# 04_MCU_ANALOG.net
KiCad netlist of a schematic drawn in Altium Designer
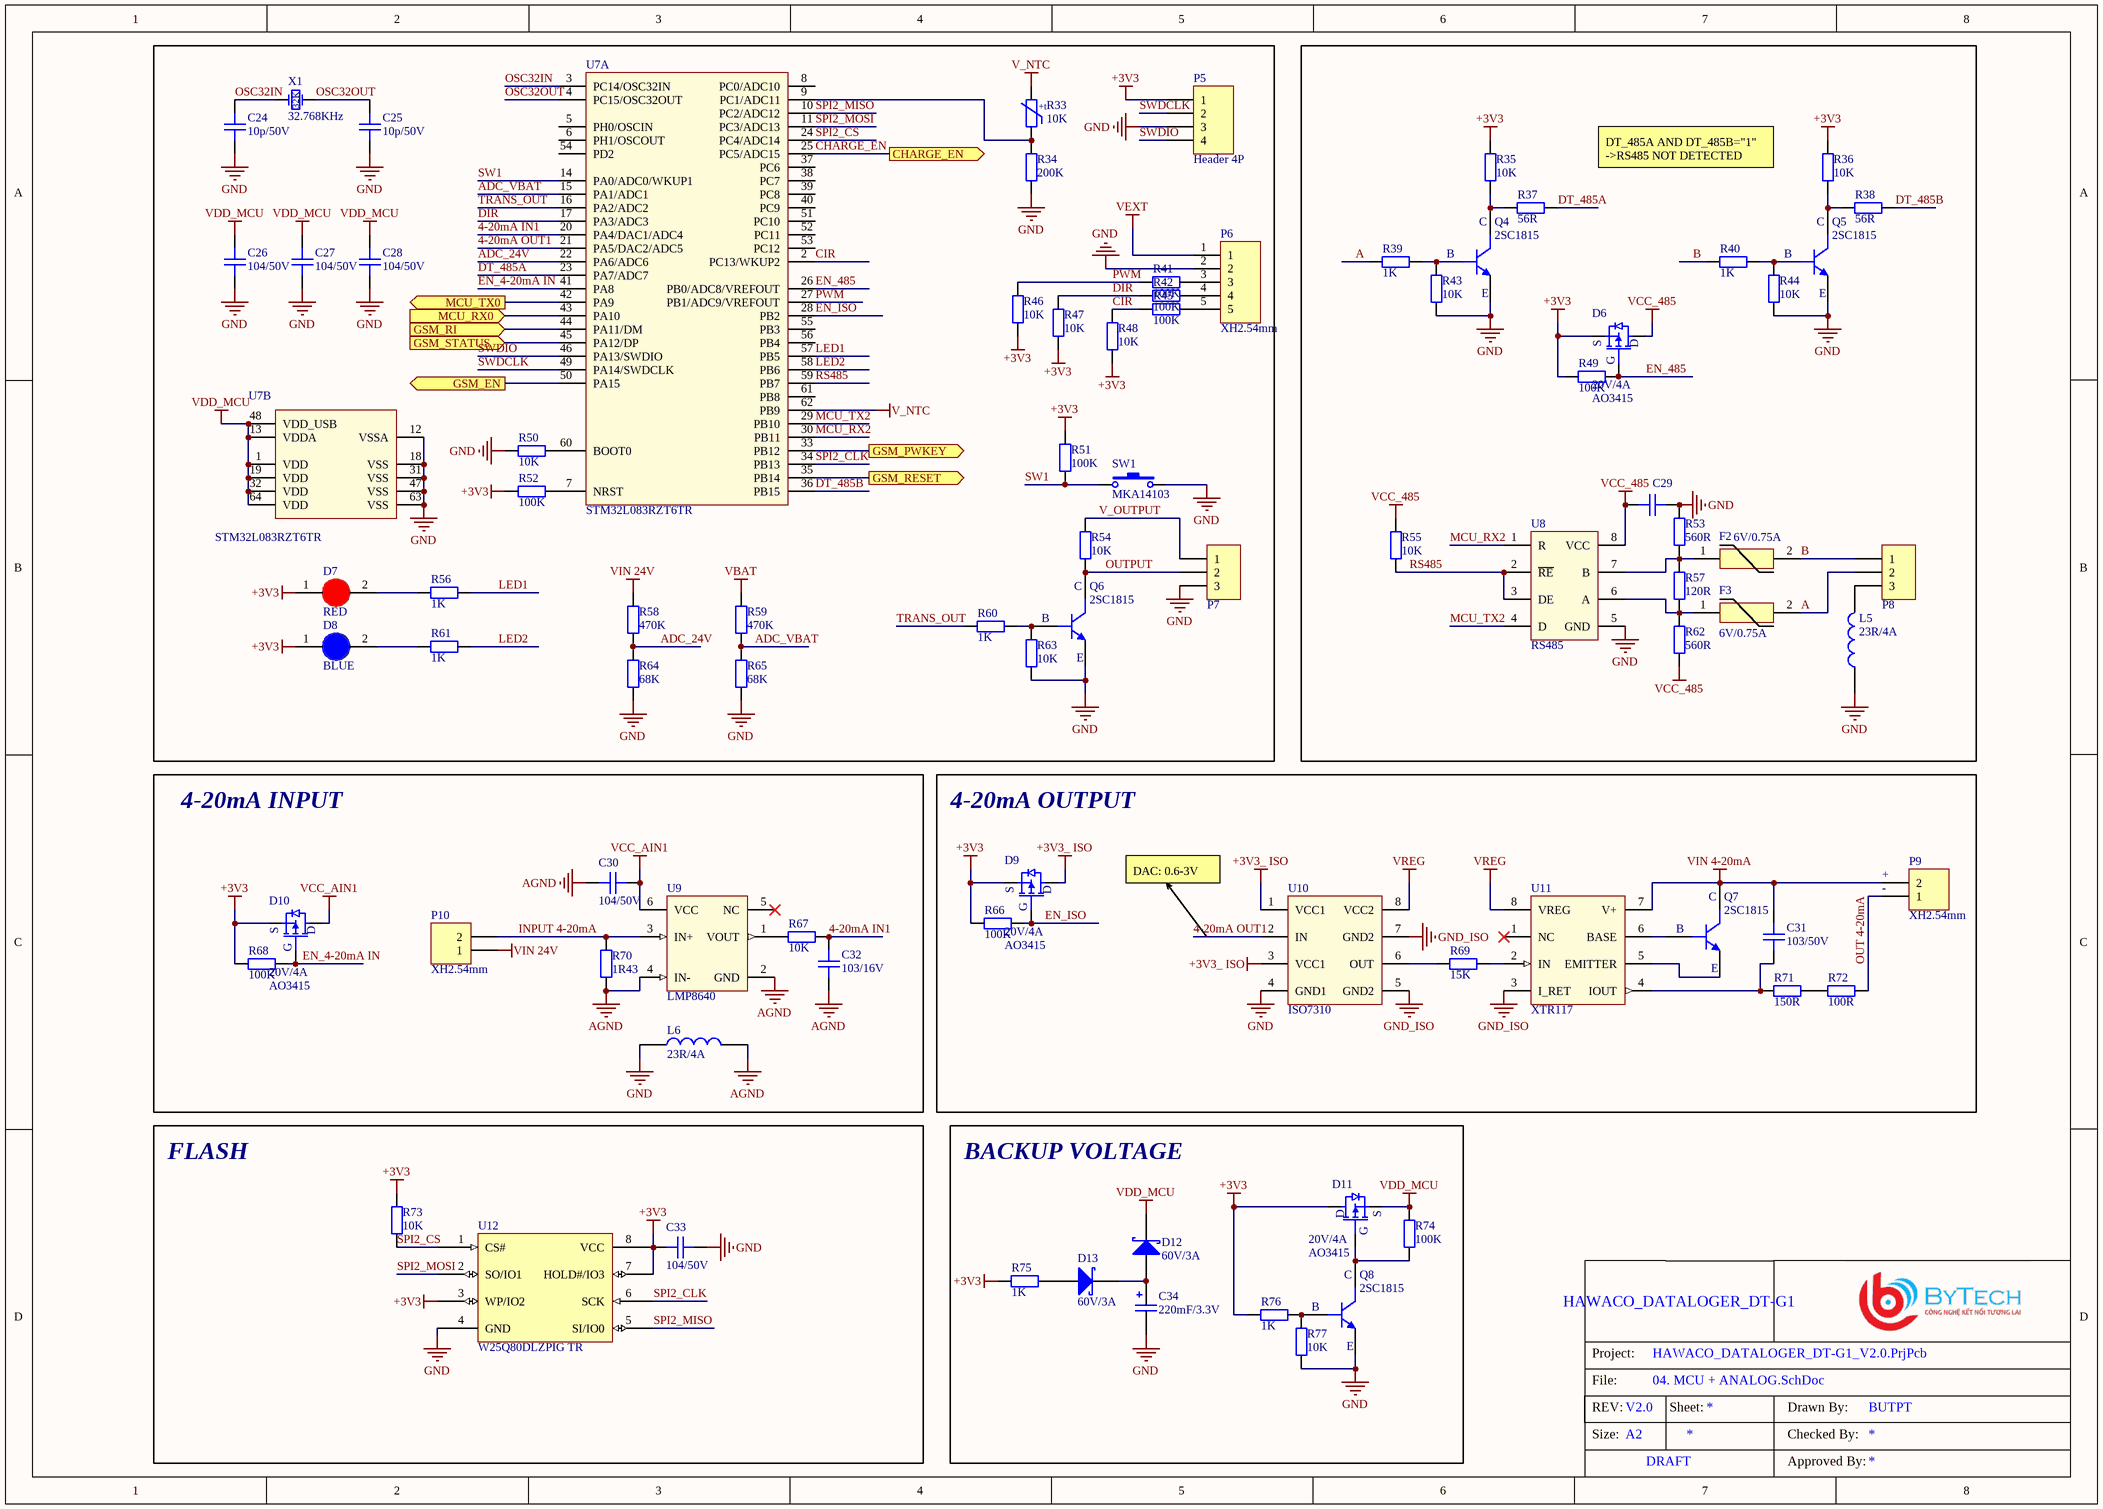
[diagram p0: 04. MCU + ANALOG.SchDoc]

(export (version "E")
  (design (tool "Eeschema 10.0.6"))
  (components
    (comp (ref "C24")
      (value "10p/50V")
      (footprint "CAPC-0603 (1608)")
      (description "CAP CER 10pF 5% 50V NP0 0603")
      (fields (field (name "MPN") "CL10C100JB8NNND"))
      (libsource (lib "01.Passives") (part "CL10C100JB8NNND"))
    )
    (comp (ref "C25")
      (value "10p/50V")
      (footprint "CAPC-0603 (1608)")
      (description "CAP CER 10pF 5% 50V NP0 0603")
      (fields (field (name "MPN") "CL10C100JB8NNND"))
      (libsource (lib "01.Passives") (part "CL10C100JB8NNND"))
    )
    (comp (ref "C26")
      (value "104/50V")
      (footprint "CAPC-0603 (1608)")
      (description "CAP CER 0.1uF 50V 10% X7R 0603")
      (fields (field (name "MPN") "C0603C104K5RACTU"))
      (libsource (lib "01.Passives") (part "C0603C104K5RACTU"))
    )
    (comp (ref "C27")
      (value "104/50V")
      (footprint "CAPC-0603 (1608)")
      (description "CAP CER 0.1uF 50V 10% X7R 0603")
      (fields (field (name "MPN") "C0603C104K5RACTU"))
      (libsource (lib "01.Passives") (part "C0603C104K5RACTU"))
    )
    (comp (ref "C28")
      (value "104/50V")
      (footprint "CAPC-0603 (1608)")
      (description "CAP CER 0.1uF 50V 10% X7R 0603")
      (fields (field (name "MPN") "C0603C104K5RACTU"))
      (libsource (lib "01.Passives") (part "C0603C104K5RACTU"))
    )
    (comp (ref "C29")
      (value "104/50V")
      (footprint "CAPC-0603 (1608)")
      (description "CAP CER 0.1uF 50V 10% X7R 0603")
      (fields (field (name "MPN") "C0603C104K5RACTU"))
      (libsource (lib "01.Passives") (part "C0603C104K5RACTU"))
    )
    (comp (ref "C30")
      (value "104/50V")
      (footprint "CAPC-0603 (1608)")
      (description "CAP CER 0.1uF 50V 10% X7R 0603")
      (fields (field (name "MPN") "C0603C104K5RACTU"))
      (libsource (lib "01.Passives") (part "C0603C104K5RACTU"))
    )
    (comp (ref "C31")
      (value "103/50V")
      (footprint "CAPC-0805 (2012)")
      (description "CAP CER 10nF 10% 50V X7R 0805")
      (fields (field (name "MPN") "CL21B103KBANNNC"))
      (libsource (lib "01.Passives") (part "CL21B103KBANNNC"))
    )
    (comp (ref "C32")
      (value "103/16V")
      (footprint "CAPC-0603 (1608)")
      (description "CAP CER 10nF 16V 10% X7R 0603")
      (fields (field (name "MPN") "CC0603KRX7R7BB103"))
      (libsource (lib "01.Passives") (part "CC0603KRX7R7BB103"))
    )
    (comp (ref "C33")
      (value "104/50V")
      (footprint "CAPC-0603 (1608)")
      (description "CAP CER 0.1uF 50V 10% X7R 0603")
      (fields (field (name "MPN") "C0603C104K5RACTU"))
      (libsource (lib "01.Passives") (part "C0603C104K5RACTU"))
    )
    (comp (ref "C34")
      (value "220mF/3.3V")
      (footprint "CAP-SUPER-0.22F")
      (description "CAP 220mF SUPER -20% +80% 3.3V SMD")
      (fields (field (name "MPN") "DCK-3R3E224U-E"))
      (libsource (lib "01.Passives") (part "DCK-3R3E224U-E"))
    )
    (comp (ref "D6")
      (value "20V/4A")
      (footprint "SOT23_3")
      (description "MOSFET P-CH 20V 4A SOT23")
      (fields (field (name "MFR") "Alpha & Omega Semiconductor Inc.") (field (name "MPN") "AO3415"))
      (libsource (lib "03.Semiconductor") (part "AO3415"))
    )
    (comp (ref "D7")
      (value "RED")
      (footprint "LED 0603")
      (description "LED 0603 RED")
      (libsource (lib "03.Semiconductor") (part "LED 0603 RED"))
    )
    (comp (ref "D8")
      (value "BLUE")
      (footprint "LED 0603")
      (description "LED 0603 BLUE")
      (libsource (lib "03.Semiconductor") (part "LED 0603 BLUE"))
    )
    (comp (ref "D9")
      (value "20V/4A")
      (footprint "SOT23_3")
      (description "MOSFET P-CH 20V 4A SOT23")
      (fields (field (name "MFR") "Alpha & Omega Semiconductor Inc.") (field (name "MPN") "AO3415"))
      (libsource (lib "03.Semiconductor") (part "AO3415"))
    )
    (comp (ref "D10")
      (value "20V/4A")
      (footprint "SOT23_3")
      (description "MOSFET P-CH 20V 4A SOT23")
      (fields (field (name "MFR") "Alpha & Omega Semiconductor Inc.") (field (name "MPN") "AO3415"))
      (libsource (lib "03.Semiconductor") (part "AO3415"))
    )
    (comp (ref "D11")
      (value "20V/4A")
      (footprint "SOT23_3")
      (description "MOSFET P-CH 20V 4A SOT23")
      (fields (field (name "MFR") "Alpha & Omega Semiconductor Inc.") (field (name "MPN") "AO3415"))
      (libsource (lib "03.Semiconductor") (part "AO3415"))
    )
    (comp (ref "D12")
      (value "60V/3A")
      (footprint "DIODE_DO214AC_SMA")
      (description "DIODE SCHOTTKY 60V 3A DO214AC")
      (fields (field (name "MPN") "SK36A-LTP"))
      (libsource (lib "03.Semiconductor") (part "SK36A-LTP"))
    )
    (comp (ref "D13")
      (value "60V/3A")
      (footprint "DIODE_DO214AC_SMA")
      (description "DIODE SCHOTTKY 60V 3A DO214AC")
      (fields (field (name "MPN") "SK36A-LTP"))
      (libsource (lib "03.Semiconductor") (part "SK36A-LTP"))
    )
    (comp (ref "F2")
      (value "6V/0.75A")
      (footprint "FUSE 0ZCK_BEL")
      (description "PTC RESET FUSE 6V 750MA 0805")
      (fields (field (name "MPN") "0ZCK0075FF2E") (field (name "MANUFACTURER") "Bel Fuse Inc."))
      (libsource (lib "02.Power,Protection") (part "0ZCK0075FF2E"))
    )
    (comp (ref "F3")
      (value "6V/0.75A")
      (footprint "FUSE 0ZCK_BEL")
      (description "PTC RESET FUSE 6V 750MA 0805")
      (fields (field (name "MPN") "0ZCK0075FF2E") (field (name "MANUFACTURER") "Bel Fuse Inc."))
      (libsource (lib "02.Power,Protection") (part "0ZCK0075FF2E"))
    )
    (comp (ref "L5")
      (value "23R/4A")
      (footprint "IND-0603 (1608)")
      (description "IND-FERRITE BEAD 23 OHM  4A 0603 1LN")
      (fields (field (name "MPN") "FBMJ1608HM230NT"))
      (libsource (lib "01.Passives") (part "FBMJ1608HM230NT"))
    )
    (comp (ref "L6")
      (value "23R/4A")
      (footprint "IND-0603 (1608)")
      (description "IND-FERRITE BEAD 23 OHM  4A 0603 1LN")
      (fields (field (name "MPN") "FBMJ1608HM230NT"))
      (libsource (lib "01.Passives") (part "FBMJ1608HM230NT"))
    )
    (comp (ref "P5")
      (value "Header 4P")
      (footprint "HDR1X4")
      (description "Header, 4 Pin Pitch 2.54mm")
      (fields (field (name "MPN") "S1012EC-40-ND"))
      (libsource (lib "04.Header-Connecter") (part "Header 4x1"))
    )
    (comp (ref "P6")
      (value "XH2.54mm")
      (footprint "XH2.54-5P")
      (description "XH2.54mmm - 5P 180 degree")
      (fields (field (name "MPN") "XH2.54-5P") (field (name "MFR") "CHINA"))
      (libsource (lib "04.Header-Connecter") (part "XH2.54-5P"))
    )
    (comp (ref "P7")
      (value "RS485")
      (footprint "XH2.54-3P")
      (description "Header XH2.54mm 3P")
      (fields (field (name "MPN") "CLA1879") (field (name "MFR") "China Brand"))
      (libsource (lib "04.Header-Connecter") (part "Header XH2.54 - 3P"))
    )
    (comp (ref "P8")
      (value "RS485")
      (footprint "XH2.54-3P")
      (description "Header XH2.54mm 3P")
      (fields (field (name "MPN") "CLA1879") (field (name "MFR") "China Brand"))
      (libsource (lib "04.Header-Connecter") (part "Header XH2.54 - 3P"))
    )
    (comp (ref "P9")
      (value "XH2.54mm")
      (footprint "XH2.54-2P")
      (description "XH2.54mmm - 2P 180 degree")
      (fields (field (name "MPN") "XH-2A"))
      (libsource (lib "04.Header-Connecter") (part "XH-2A"))
    )
    (comp (ref "P10")
      (value "XH2.54mm")
      (footprint "XH2.54-2P")
      (description "XH2.54mmm - 2P 180 degree")
      (fields (field (name "MPN") "XH-2A"))
      (libsource (lib "") (part "XH-2A_1"))
    )
    (comp (ref "Q4")
      (value "2SC1815")
      (footprint "SOT23_3")
      (description "TRANS NPN 50V 0.15A SOT23-3")
      (libsource (lib "03.Semiconductor") (part "2SC1815"))
    )
    (comp (ref "Q5")
      (value "2SC1815")
      (footprint "SOT23_3")
      (description "TRANS NPN 50V 0.15A SOT23-3")
      (libsource (lib "03.Semiconductor") (part "2SC1815"))
    )
    (comp (ref "Q6")
      (value "2SC1815")
      (footprint "SOT23_3")
      (description "TRANS NPN 50V 0.15A SOT23-3")
      (libsource (lib "03.Semiconductor") (part "2SC1815"))
    )
    (comp (ref "Q7")
      (value "2SC1815")
      (footprint "SOT23_3")
      (description "TRANS NPN 50V 0.15A SOT23-3")
      (libsource (lib "03.Semiconductor") (part "2SC1815"))
    )
    (comp (ref "Q8")
      (value "2SC1815")
      (footprint "SOT23_3")
      (description "TRANS NPN 50V 0.15A SOT23-3")
      (libsource (lib "03.Semiconductor") (part "2SC1815"))
    )
    (comp (ref "R33")
      (value "10K")
      (footprint "RES NTC 10K")
      (description "THERMISTOR NTC 10KOHM 3964K BEAD")
      (fields (field (name "MPN") "01M1002JF") (field (name "MFR") "Vishay"))
      (libsource (lib "01.Passives") (part "01M1002JF"))
    )
    (comp (ref "R34")
      (value "200K")
      (footprint "RESC-0603 (1608)")
      (description "RES SMD 200K OHM 1% 1/10W 0603")
      (fields (field (name "MPN") "CR0603-FX-2003ELF"))
      (libsource (lib "01.Passives") (part "CR0603-FX-2003ELF"))
    )
    (comp (ref "R35")
      (value "10K")
      (footprint "RESC-0603 (1608)")
      (description "RES SMD 10K OHM 1% 1/10W 0603")
      (fields (field (name "MPN") "RC0603FR-0710KL"))
      (libsource (lib "01.Passives") (part "RC0603FR-0710KL"))
    )
    (comp (ref "R36")
      (value "10K")
      (footprint "RESC-0603 (1608)")
      (description "RES SMD 10K OHM 1% 1/10W 0603")
      (fields (field (name "MPN") "RC0603FR-0710KL"))
      (libsource (lib "01.Passives") (part "RC0603FR-0710KL"))
    )
    (comp (ref "R37")
      (value "56R")
      (footprint "RESC-0603 (1608)")
      (description "RES SMD 56 OHM 5% 1/10W 0603")
      (fields (field (name "MPN") "RC0603JR-0756RL"))
      (libsource (lib "01.Passives") (part "RC0603JR-0756RL"))
    )
    (comp (ref "R38")
      (value "56R")
      (footprint "RESC-0603 (1608)")
      (description "RES SMD 56 OHM 5% 1/10W 0603")
      (fields (field (name "MPN") "RC0603JR-0756RL"))
      (libsource (lib "01.Passives") (part "RC0603JR-0756RL"))
    )
    (comp (ref "R39")
      (value "1K")
      (footprint "RESC-0603 (1608)")
      (description "RES SMD 1 KOHM 1% 1/10W 0603")
      (fields (field (name "MPN") "RC0603FR-071KL"))
      (libsource (lib "01.Passives") (part "RC0603FR-071KL"))
    )
    (comp (ref "R40")
      (value "1K")
      (footprint "RESC-0603 (1608)")
      (description "RES SMD 1 KOHM 1% 1/10W 0603")
      (fields (field (name "MPN") "RC0603FR-071KL"))
      (libsource (lib "01.Passives") (part "RC0603FR-071KL"))
    )
    (comp (ref "R41")
      (value "100K")
      (footprint "RESC-0603 (1608)")
      (description "RES SMD 100K OHM 1% 1/10W 0603")
      (fields (field (name "MPN") "RC0603FR-07100KL"))
      (libsource (lib "") (part "RC0603FR-07100KL_3"))
    )
    (comp (ref "R42")
      (value "100K")
      (footprint "RESC-0603 (1608)")
      (description "RES SMD 100K OHM 1% 1/10W 0603")
      (fields (field (name "MPN") "RC0603FR-07100KL"))
      (libsource (lib "") (part "RC0603FR-07100KL_3"))
    )
    (comp (ref "R43")
      (value "10K")
      (footprint "RESC-0603 (1608)")
      (description "RES SMD 10K OHM 1% 1/10W 0603")
      (fields (field (name "MPN") "RC0603FR-0710KL"))
      (libsource (lib "01.Passives") (part "RC0603FR-0710KL"))
    )
    (comp (ref "R44")
      (value "10K")
      (footprint "RESC-0603 (1608)")
      (description "RES SMD 10K OHM 1% 1/10W 0603")
      (fields (field (name "MPN") "RC0603FR-0710KL"))
      (libsource (lib "01.Passives") (part "RC0603FR-0710KL"))
    )
    (comp (ref "R45")
      (value "100K")
      (footprint "RESC-0603 (1608)")
      (description "RES SMD 100K OHM 1% 1/10W 0603")
      (fields (field (name "MPN") "RC0603FR-07100KL"))
      (libsource (lib "") (part "RC0603FR-07100KL_3"))
    )
    (comp (ref "R46")
      (value "10K")
      (footprint "RESC-0603 (1608)")
      (description "RES SMD 10K OHM 1% 1/10W 0603")
      (fields (field (name "MPN") "RC0603FR-0710KL"))
      (libsource (lib "01.Passives") (part "RC0603FR-0710KL"))
    )
    (comp (ref "R47")
      (value "10K")
      (footprint "RESC-0603 (1608)")
      (description "RES SMD 10K OHM 1% 1/10W 0603")
      (fields (field (name "MPN") "RC0603FR-0710KL"))
      (libsource (lib "01.Passives") (part "RC0603FR-0710KL"))
    )
    (comp (ref "R48")
      (value "10K")
      (footprint "RESC-0603 (1608)")
      (description "RES SMD 10K OHM 1% 1/10W 0603")
      (fields (field (name "MPN") "RC0603FR-0710KL"))
      (libsource (lib "01.Passives") (part "RC0603FR-0710KL"))
    )
    (comp (ref "R49")
      (value "100K")
      (footprint "RESC-0603 (1608)")
      (description "RES SMD 100K OHM 1% 1/10W 0603")
      (fields (field (name "MPN") "RC0603FR-07100KL"))
      (libsource (lib "") (part "RC0603FR-07100KL_1"))
    )
    (comp (ref "R50")
      (value "10K")
      (footprint "RESC-0603 (1608)")
      (description "RES SMD 10K OHM 1% 1/10W 0603")
      (fields (field (name "MPN") "RC0603FR-0710KL"))
      (libsource (lib "") (part "RC0603FR-0710KL_1"))
    )
    (comp (ref "R51")
      (value "100K")
      (footprint "RESC-0603 (1608)")
      (description "RES SMD 100K OHM 1% 1/10W 0603")
      (fields (field (name "MPN") "RC0603FR-07100KL"))
      (libsource (lib "01.Passives") (part "RC0603FR-07100KL"))
    )
    (comp (ref "R52")
      (value "100K")
      (footprint "RESC-0603 (1608)")
      (description "RES SMD 100K OHM 1% 1/10W 0603")
      (fields (field (name "MPN") "RC0603FR-07100KL"))
      (libsource (lib "01.Passives") (part "RC0603FR-07100KL"))
    )
    (comp (ref "R53")
      (value "560R")
      (footprint "RESC-0603 (1608)")
      (description "RES SMD 560 OHM 1% 1/10W 0603")
      (fields (field (name "MPN") "RC0603FR-07560RL"))
      (libsource (lib "01.Passives") (part "RC0603FR-07560RL"))
    )
    (comp (ref "R54")
      (value "10K")
      (footprint "RESC-0603 (1608)")
      (description "RES SMD 10K OHM 1% 1/10W 0603")
      (fields (field (name "MPN") "RC0603FR-0710KL"))
      (libsource (lib "01.Passives") (part "RC0603FR-0710KL"))
    )
    (comp (ref "R55")
      (value "10K")
      (footprint "RESC-0603 (1608)")
      (description "RES SMD 10K OHM 1% 1/10W 0603")
      (fields (field (name "MPN") "RC0603FR-0710KL"))
      (libsource (lib "01.Passives") (part "RC0603FR-0710KL"))
    )
    (comp (ref "R56")
      (value "1K")
      (footprint "RESC-0603 (1608)")
      (description "RES SMD 1 KOHM 1% 1/10W 0603")
      (fields (field (name "MPN") "RC0603FR-071KL"))
      (libsource (lib "01.Passives") (part "RC0603FR-071KL"))
    )
    (comp (ref "R57")
      (value "120R")
      (footprint "RESC-0603 (1608)")
      (description "RES SMD 120 OHM 1% 1/10W 0603")
      (fields (field (name "MPN") "RC0603FR-07120RL"))
      (libsource (lib "01.Passives") (part "RC0603FR-07120RL"))
    )
    (comp (ref "R58")
      (value "470K")
      (footprint "RESC-0603 (1608)")
      (description "RES SMD 470K OHM 1% 1/10W 0603")
      (fields (field (name "MPN") "RC0603FR-07470K"))
      (libsource (lib "01.Passives") (part "RC0603FR-07470KL"))
    )
    (comp (ref "R59")
      (value "470K")
      (footprint "RESC-0603 (1608)")
      (description "RES SMD 470K OHM 1% 1/10W 0603")
      (fields (field (name "MPN") "RC0603FR-07470K"))
      (libsource (lib "01.Passives") (part "RC0603FR-07470KL"))
    )
    (comp (ref "R60")
      (value "1K")
      (footprint "RESC-0603 (1608)")
      (description "RES SMD 1 KOHM 1% 1/10W 0603")
      (fields (field (name "MPN") "RC0603FR-071KL"))
      (libsource (lib "01.Passives") (part "RC0603FR-071KL"))
    )
    (comp (ref "R61")
      (value "1K")
      (footprint "RESC-0603 (1608)")
      (description "RES SMD 1 KOHM 1% 1/10W 0603")
      (fields (field (name "MPN") "RC0603FR-071KL"))
      (libsource (lib "01.Passives") (part "RC0603FR-071KL"))
    )
    (comp (ref "R62")
      (value "560R")
      (footprint "RESC-0603 (1608)")
      (description "RES SMD 560 OHM 1% 1/10W 0603")
      (fields (field (name "MPN") "RC0603FR-07560RL"))
      (libsource (lib "01.Passives") (part "RC0603FR-07560RL"))
    )
    (comp (ref "R63")
      (value "10K")
      (footprint "RESC-0603 (1608)")
      (description "RES SMD 10K OHM 1% 1/10W 0603")
      (fields (field (name "MPN") "RC0603FR-0710KL"))
      (libsource (lib "01.Passives") (part "RC0603FR-0710KL"))
    )
    (comp (ref "R64")
      (value "68K")
      (footprint "RESC-0603 (1608)")
      (description "RES SMD 68K OHM 1% 1/10W 0603")
      (fields (field (name "MPN") "CRCW060368K0FKEA"))
      (libsource (lib "01.Passives") (part "CRCW060368K0FKEA"))
    )
    (comp (ref "R65")
      (value "68K")
      (footprint "RESC-0603 (1608)")
      (description "RES SMD 68K OHM 1% 1/10W 0603")
      (fields (field (name "MPN") "CRCW060368K0FKEA"))
      (libsource (lib "01.Passives") (part "CRCW060368K0FKEA"))
    )
    (comp (ref "R66")
      (value "100K")
      (footprint "RESC-0603 (1608)")
      (description "RES SMD 100K OHM 1% 1/10W 0603")
      (fields (field (name "MPN") "RC0603FR-07100KL"))
      (libsource (lib "") (part "RC0603FR-07100KL_1"))
    )
    (comp (ref "R67")
      (value "10K")
      (footprint "RESC-0603 (1608)")
      (description "RES SMD 10K OHM 1% 1/10W 0603")
      (fields (field (name "MPN") "RC0603FR-0710KL"))
      (libsource (lib "") (part "RC0603FR-0710KL_2"))
    )
    (comp (ref "R68")
      (value "100K")
      (footprint "RESC-0603 (1608)")
      (description "RES SMD 100K OHM 1% 1/10W 0603")
      (fields (field (name "MPN") "RC0603FR-07100KL"))
      (libsource (lib "") (part "RC0603FR-07100KL_1"))
    )
    (comp (ref "R69")
      (value "15K")
      (footprint "RESC-0603 (1608)")
      (description "RES SMD 15K OHM 0.1% 1/10W 0603")
      (fields (field (name "MPN") "RT0603BRE-0715KL"))
      (libsource (lib "01.Passives") (part "RT0603BRE-0715KL"))
    )
    (comp (ref "R70")
      (value "1R43")
      (footprint "RESC-0603 (1608)")
      (description "RES SMD 1.43 OHM 0.1% 1/10W 0603")
      (fields (field (name "MPN") "RT0603BRE071R43L") (field (name "MFR") "YAGEO"))
      (libsource (lib "01.Passives") (part "RT0603BRE071R43L"))
    )
    (comp (ref "R71")
      (value "150R")
      (footprint "RESC-0603 (1608)")
      (description "RES SMD 150 OHM 1% 1/10W 0603")
      (fields (field (name "MPN") "RC0603FR-07150RP") (field (name "MFR") "YAGEO"))
      (libsource (lib "01.Passives") (part "RC0603FR-07150RP"))
    )
    (comp (ref "R72")
      (value "100R")
      (footprint "RESC-0603 (1608)")
      (description "RES SMD 100 OHM 1% 1/10W 0603")
      (fields (field (name "MPN") "RC0603FR-07100RL"))
      (libsource (lib "01.Passives") (part "RC0603FR-07100RL"))
    )
    (comp (ref "R73")
      (value "10K")
      (footprint "RESC-0603 (1608)")
      (description "RES SMD 10K OHM 1% 1/10W 0603")
      (fields (field (name "MPN") "RC0603FR-0710KL"))
      (libsource (lib "") (part "RC0603FR-0710KL_1"))
    )
    (comp (ref "R74")
      (value "100K")
      (footprint "RESC-0603 (1608)")
      (description "RES SMD 100K OHM 1% 1/10W 0603")
      (fields (field (name "MPN") "RC0603FR-07100KL"))
      (libsource (lib "") (part "RC0603FR-07100KL_2"))
    )
    (comp (ref "R75")
      (value "1K")
      (footprint "RESC-0603 (1608)")
      (description "RES SMD 1 KOHM 1% 1/10W 0603")
      (fields (field (name "MPN") "RC0603FR-071KL"))
      (libsource (lib "") (part "RC0603FR-071KL_1"))
    )
    (comp (ref "R76")
      (value "1K")
      (footprint "RESC-0603 (1608)")
      (description "RES SMD 1 KOHM 1% 1/10W 0603")
      (fields (field (name "MPN") "RC0603FR-071KL"))
      (libsource (lib "01.Passives") (part "RC0603FR-071KL"))
    )
    (comp (ref "R77")
      (value "10K")
      (footprint "RESC-0603 (1608)")
      (description "RES SMD 10K OHM 1% 1/10W 0603")
      (fields (field (name "MPN") "RC0603FR-0710KL"))
      (libsource (lib "01.Passives") (part "RC0603FR-0710KL"))
    )
    (comp (ref "SW1")
      (value "MKA14103")
      (footprint "MKA-14103")
      (description "switch magnetic control switch 14103 2*14MM")
      (fields (field (name "MFR") "CHINA"))
      (libsource (lib "08.Miscellaneous") (part "MKA14103"))
    )
    (comp (ref "U7")
      (value "STM32L083RZT6TR")
      (footprint "LQFP-64")
      (description "IC MCU 32BIT 192KB FLASH 64LQFP")
      (fields (field (name "MFR") "ST"))
      (libsource (lib "05.IC") (part "STM32L083RZT6TR"))
    )
    (comp (ref "U8")
      (value "RS485")
      (footprint "SOIC8")
      (description "IC TRANSCEIVER HALF 1/1 8SOIC")
      (fields (field (name "MPN") "SN65HVD72DR") (field (name "MFR") "TI"))
      (libsource (lib "05.IC") (part "SN65HVD72DR"))
    )
    (comp (ref "U9")
      (value "LMP8640")
      (footprint "SOT23-6")
      (description "IC CURR SENSE 1 CIRCUIT TSOT23-6")
      (fields (field (name "MPN") "LMP8640MK-H/NOPB") (field (name "MFR") "TI"))
      (libsource (lib "05.IC") (part "LMP8640MK-H/NOPB"))
    )
    (comp (ref "U10")
      (value "ISO7310")
      (footprint "SOIC-8")
      (description "DGTL ISO 3000VRMS 1CH 8SOIC")
      (fields (field (name "MPN") "ISO7310CQDRQ1") (field (name "MFR") "TI"))
      (libsource (lib "05.IC") (part "ISO7310CQDRQ1"))
    )
    (comp (ref "U11")
      (value "XTR117")
      (footprint "8VSSOP")
      (description "IC CURRENT TRANSMITTER 8VSSOP")
      (fields (field (name "MPN") "XTR117AIDGKR") (field (name "MFR") "Texas Instruments"))
      (libsource (lib "05.IC") (part "XTR117AIDGKR"))
    )
    (comp (ref "U12")
      (value "W25Q80DLZPIG TR")
      (footprint "WSON-8 6X5MM")
      (description "IC FLSH 8MBIT SPI/QUAD I/O 8WSON")
      (fields (field (name "MFR") "Winbond Electronics"))
      (libsource (lib "05.IC") (part "W25Q80DLZPIG TR"))
    )
    (comp (ref "X1")
      (value "32.768KHz")
      (footprint "CRYSTAL_ABS06 2x1.2mm")
      (description "CRYSTAL 32.7680KHZ 4pF SMD")
      (fields (field (name "MPN") "ABS06-107-32.768kHz-T"))
      (libsource (lib "01.Passives") (part "ABS06-107-32.768kHz-T"))
    )
  )
  (nets
    (net (code "1") (name "+3V3") (class "Default")
      (node (ref "C33") (pin "2") (pinfunction "2_2") (pintype "passive"))
      (node (ref "D10") (pin "2") (pinfunction "S_2") (pintype "passive"))
      (node (ref "D11") (pin "3") (pinfunction "D_3") (pintype "passive"))
      (node (ref "D6") (pin "2") (pinfunction "S_2") (pintype "passive"))
      (node (ref "D7") (pin "1") (pinfunction "A_1") (pintype "passive"))
      (node (ref "D8") (pin "1") (pinfunction "A_1") (pintype "passive"))
      (node (ref "D9") (pin "2") (pinfunction "S_2") (pintype "passive"))
      (node (ref "P5") (pin "1") (pinfunction "1_1") (pintype "passive"))
      (node (ref "R35") (pin "2") (pinfunction "2_2") (pintype "passive"))
      (node (ref "R36") (pin "2") (pinfunction "2_2") (pintype "passive"))
      (node (ref "R46") (pin "1") (pinfunction "1_1") (pintype "passive"))
      (node (ref "R47") (pin "1") (pinfunction "1_1") (pintype "passive"))
      (node (ref "R48") (pin "1") (pinfunction "1_1") (pintype "passive"))
      (node (ref "R49") (pin "2") (pinfunction "2_2") (pintype "passive"))
      (node (ref "R51") (pin "2") (pinfunction "2_2") (pintype "passive"))
      (node (ref "R52") (pin "1") (pinfunction "1_1") (pintype "passive"))
      (node (ref "R66") (pin "2") (pinfunction "2_2") (pintype "passive"))
      (node (ref "R68") (pin "2") (pinfunction "2_2") (pintype "passive"))
      (node (ref "R73") (pin "1") (pinfunction "1_1") (pintype "passive"))
      (node (ref "R75") (pin "2") (pinfunction "2_2") (pintype "passive"))
      (node (ref "R76") (pin "1") (pinfunction "1_1") (pintype "passive"))
      (node (ref "U12") (pin "3") (pinfunction "WP/IO2_3") (pintype "bidirectional"))
      (node (ref "U12") (pin "7") (pinfunction "HOLD#/IO3_7") (pintype "bidirectional"))
      (node (ref "U12") (pin "8") (pinfunction "VCC_8") (pintype "power_in"))
    )
    (net (code "2") (name "+3V3_ ISO") (class "Default")
      (node (ref "D9") (pin "3") (pinfunction "D_3") (pintype "passive"))
      (node (ref "U10") (pin "1") (pinfunction "VCC1_1") (pintype "passive"))
      (node (ref "U10") (pin "3") (pinfunction "VCC1_3") (pintype "passive"))
    )
    (net (code "3") (name "/4-20mA IN1") (class "Default")
      (node (ref "C32") (pin "2") (pinfunction "2_2") (pintype "passive"))
      (node (ref "R67") (pin "1") (pinfunction "1_1") (pintype "passive"))
      (node (ref "U7") (pin "20") (pinfunction "PA4/DAC1/ADC4_20") (pintype "passive"))
    )
    (net (code "4") (name "/4-20mA OUT1") (class "Default")
      (node (ref "U10") (pin "2") (pinfunction "IN_2") (pintype "passive"))
      (node (ref "U7") (pin "21") (pinfunction "PA5/DAC2/ADC5_21") (pintype "passive"))
    )
    (net (code "5") (name "/A") (class "Default")
      (node (ref "F3") (pin "2") (pinfunction "2_2") (pintype "passive"))
      (node (ref "P8") (pin "2") (pinfunction "2_2") (pintype "passive"))
      (node (ref "R39") (pin "1") (pinfunction "1_1") (pintype "passive"))
    )
    (net (code "6") (name "/ADC_24V") (class "Default")
      (node (ref "R58") (pin "1") (pinfunction "1_1") (pintype "passive"))
      (node (ref "R64") (pin "2") (pinfunction "2_2") (pintype "passive"))
      (node (ref "U7") (pin "22") (pinfunction "PA6/ADC6_22") (pintype "passive"))
    )
    (net (code "7") (name "/ADC_VBAT") (class "Default")
      (node (ref "R59") (pin "1") (pinfunction "1_1") (pintype "passive"))
      (node (ref "R65") (pin "2") (pinfunction "2_2") (pintype "passive"))
      (node (ref "U7") (pin "15") (pinfunction "PA1/ADC1_15") (pintype "passive"))
    )
    (net (code "8") (name "/B") (class "Default")
      (node (ref "F2") (pin "2") (pinfunction "2_2") (pintype "passive"))
      (node (ref "P8") (pin "1") (pinfunction "1_1") (pintype "passive"))
      (node (ref "R40") (pin "1") (pinfunction "1_1") (pintype "passive"))
    )
    (net (code "9") (name "/CHARGE_EN") (class "Default")
      (node (ref "U7") (pin "25") (pinfunction "PC5/ADC15_25") (pintype "passive"))
    )
    (net (code "10") (name "/CIR") (class "Default")
      (node (ref "R45") (pin "1") (pinfunction "1_1") (pintype "passive"))
      (node (ref "R48") (pin "2") (pinfunction "2_2") (pintype "passive"))
      (node (ref "U7") (pin "2") (pinfunction "PC13/WKUP2_2") (pintype "passive"))
    )
    (net (code "11") (name "/DIR") (class "Default")
      (node (ref "R42") (pin "1") (pinfunction "1_1") (pintype "passive"))
      (node (ref "R47") (pin "2") (pinfunction "2_2") (pintype "passive"))
      (node (ref "U7") (pin "17") (pinfunction "PA3/ADC3_17") (pintype "passive"))
    )
    (net (code "12") (name "/DT_485A") (class "Default")
      (node (ref "R37") (pin "2") (pinfunction "2_2") (pintype "passive"))
      (node (ref "U7") (pin "23") (pinfunction "PA7/ADC7_23") (pintype "passive"))
    )
    (net (code "13") (name "/DT_485B") (class "Default")
      (node (ref "R38") (pin "2") (pinfunction "2_2") (pintype "passive"))
      (node (ref "U7") (pin "36") (pinfunction "PB15_36") (pintype "passive"))
    )
    (net (code "14") (name "/EN_4-20mA IN") (class "Default")
      (node (ref "D10") (pin "1") (pinfunction "G_1") (pintype "passive"))
      (node (ref "R68") (pin "1") (pinfunction "1_1") (pintype "passive"))
      (node (ref "U7") (pin "41") (pinfunction "PA8_41") (pintype "passive"))
    )
    (net (code "15") (name "/EN_485") (class "Default")
      (node (ref "D6") (pin "1") (pinfunction "G_1") (pintype "passive"))
      (node (ref "R49") (pin "1") (pinfunction "1_1") (pintype "passive"))
      (node (ref "U7") (pin "26") (pinfunction "PB0/ADC8/VREFOUT_26") (pintype "passive"))
    )
    (net (code "16") (name "/EN_ISO") (class "Default")
      (node (ref "D9") (pin "1") (pinfunction "G_1") (pintype "passive"))
      (node (ref "R66") (pin "1") (pinfunction "1_1") (pintype "passive"))
      (node (ref "U7") (pin "28") (pinfunction "PB2_28") (pintype "passive"))
    )
    (net (code "17") (name "/GSM_EN") (class "Default")
      (node (ref "U7") (pin "50") (pinfunction "PA15_50") (pintype "passive"))
    )
    (net (code "18") (name "/GSM_PWKEY") (class "Default")
      (node (ref "U7") (pin "33") (pinfunction "PB12_33") (pintype "passive"))
    )
    (net (code "19") (name "/GSM_RESET") (class "Default")
      (node (ref "U7") (pin "35") (pinfunction "PB14_35") (pintype "passive"))
    )
    (net (code "20") (name "/GSM_RI") (class "Default")
      (node (ref "U7") (pin "44") (pinfunction "PA11/DM_44") (pintype "passive"))
    )
    (net (code "21") (name "/GSM_STATUS") (class "Default")
      (node (ref "U7") (pin "45") (pinfunction "PA12/DP_45") (pintype "passive"))
    )
    (net (code "22") (name "/INPUT 4-20mA") (class "Default")
      (node (ref "P10") (pin "2") (pinfunction "2_2") (pintype "passive"))
      (node (ref "R70") (pin "2") (pinfunction "2_2") (pintype "passive"))
      (node (ref "U9") (pin "3") (pinfunction "IN+_3") (pintype "input"))
    )
    (net (code "23") (name "/LED1") (class "Default")
      (node (ref "R56") (pin "2") (pinfunction "2_2") (pintype "passive"))
      (node (ref "U7") (pin "57") (pinfunction "PB5_57") (pintype "passive"))
    )
    (net (code "24") (name "/LED2") (class "Default")
      (node (ref "R61") (pin "2") (pinfunction "2_2") (pintype "passive"))
      (node (ref "U7") (pin "58") (pinfunction "PB6_58") (pintype "passive"))
    )
    (net (code "25") (name "/MCU_RX0") (class "Default")
      (node (ref "U7") (pin "43") (pinfunction "PA10_43") (pintype "passive"))
    )
    (net (code "26") (name "/MCU_RX2") (class "Default")
      (node (ref "U7") (pin "30") (pinfunction "PB11_30") (pintype "passive"))
      (node (ref "U8") (pin "1") (pinfunction "R_1") (pintype "power_in"))
    )
    (net (code "27") (name "/MCU_TX0") (class "Default")
      (node (ref "U7") (pin "42") (pinfunction "PA9_42") (pintype "passive"))
    )
    (net (code "28") (name "/MCU_TX2") (class "Default")
      (node (ref "U7") (pin "29") (pinfunction "PB10_29") (pintype "passive"))
      (node (ref "U8") (pin "4") (pinfunction "D_4") (pintype "power_in"))
    )
    (net (code "29") (name "/OSC32IN") (class "Default")
      (node (ref "C24") (pin "2") (pinfunction "2_2") (pintype "passive"))
      (node (ref "U7") (pin "3") (pinfunction "PC14/OSC32IN_3") (pintype "passive"))
      (node (ref "X1") (pin "1") (pinfunction "OSC1_1") (pintype "passive"))
    )
    (net (code "30") (name "/OSC32OUT") (class "Default")
      (node (ref "C25") (pin "2") (pinfunction "2_2") (pintype "passive"))
      (node (ref "U7") (pin "4") (pinfunction "PC15/OSC32OUT_4") (pintype "passive"))
      (node (ref "X1") (pin "2") (pinfunction "OSC2_2") (pintype "passive"))
    )
    (net (code "31") (name "/OUT 4-20mA") (class "Default")
      (node (ref "P9") (pin "1") (pinfunction "1_1") (pintype "passive"))
      (node (ref "R72") (pin "2") (pinfunction "2_2") (pintype "passive"))
    )
    (net (code "32") (name "/OUTPUT") (class "Default")
      (node (ref "P7") (pin "2") (pinfunction "2_2") (pintype "passive"))
      (node (ref "Q6") (pin "3") (pinfunction "C_3") (pintype "passive"))
      (node (ref "R54") (pin "1") (pinfunction "1_1") (pintype "passive"))
    )
    (net (code "33") (name "/PWM") (class "Default")
      (node (ref "R41") (pin "1") (pinfunction "1_1") (pintype "passive"))
      (node (ref "R46") (pin "2") (pinfunction "2_2") (pintype "passive"))
      (node (ref "U7") (pin "27") (pinfunction "PB1/ADC9/VREFOUT_27") (pintype "passive"))
    )
    (net (code "34") (name "/RS485") (class "Default")
      (node (ref "R55") (pin "1") (pinfunction "1_1") (pintype "passive"))
      (node (ref "U7") (pin "59") (pinfunction "PB7_59") (pintype "passive"))
      (node (ref "U8") (pin "2") (pinfunction "~{RE}_2") (pintype "power_in"))
      (node (ref "U8") (pin "3") (pinfunction "DE_3") (pintype "power_in"))
    )
    (net (code "35") (name "/SPI2_CLK") (class "Default")
      (node (ref "U12") (pin "6") (pinfunction "SCK_6") (pintype "input"))
      (node (ref "U7") (pin "34") (pinfunction "PB13_34") (pintype "passive"))
    )
    (net (code "36") (name "/SPI2_CS") (class "Default")
      (node (ref "R73") (pin "2") (pinfunction "2_2") (pintype "passive"))
      (node (ref "U12") (pin "1") (pinfunction "CS#_1") (pintype "input"))
      (node (ref "U7") (pin "24") (pinfunction "PC4/ADC14_24") (pintype "passive"))
    )
    (net (code "37") (name "/SPI2_MISO") (class "Default")
      (node (ref "U12") (pin "5") (pinfunction "SI/IO0_5") (pintype "bidirectional"))
      (node (ref "U7") (pin "10") (pinfunction "PC2/ADC12_10") (pintype "passive"))
    )
    (net (code "38") (name "/SPI2_MOSI") (class "Default")
      (node (ref "U12") (pin "2") (pinfunction "SO/IO1_2") (pintype "bidirectional"))
      (node (ref "U7") (pin "11") (pinfunction "PC3/ADC13_11") (pintype "passive"))
    )
    (net (code "39") (name "/SW1") (class "Default")
      (node (ref "R51") (pin "1") (pinfunction "1_1") (pintype "passive"))
      (node (ref "SW1") (pin "1") (pinfunction "1_1") (pintype "passive"))
      (node (ref "U7") (pin "14") (pinfunction "PA0/ADC0/WKUP1_14") (pintype "passive"))
    )
    (net (code "40") (name "/SWDCLK") (class "Default")
      (node (ref "P5") (pin "2") (pinfunction "2_2") (pintype "passive"))
      (node (ref "U7") (pin "49") (pinfunction "PA14/SWDCLK_49") (pintype "passive"))
    )
    (net (code "41") (name "/SWDIO") (class "Default")
      (node (ref "P5") (pin "4") (pinfunction "4_4") (pintype "passive"))
      (node (ref "U7") (pin "46") (pinfunction "PA13/SWDIO_46") (pintype "passive"))
    )
    (net (code "42") (name "/TRANS_OUT") (class "Default")
      (node (ref "R60") (pin "1") (pinfunction "1_1") (pintype "passive"))
      (node (ref "U7") (pin "16") (pinfunction "PA2/ADC2_16") (pintype "passive"))
    )
    (net (code "43") (name "/V_OUTPUT") (class "Default")
      (node (ref "P7") (pin "1") (pinfunction "1_1") (pintype "passive"))
      (node (ref "R54") (pin "2") (pinfunction "2_2") (pintype "passive"))
    )
    (net (code "44") (name "AGND") (class "Default")
      (node (ref "C30") (pin "2") (pinfunction "2_2") (pintype "passive"))
      (node (ref "C32") (pin "1") (pinfunction "1_1") (pintype "passive"))
      (node (ref "L6") (pin "2") (pinfunction "2_2") (pintype "passive"))
      (node (ref "R70") (pin "1") (pinfunction "1_1") (pintype "passive"))
      (node (ref "U9") (pin "2") (pinfunction "GND_2") (pintype "power_in"))
      (node (ref "U9") (pin "4") (pinfunction "IN-_4") (pintype "input"))
    )
    (net (code "45") (name "GND") (class "Default")
      (node (ref "C24") (pin "1") (pinfunction "1_1") (pintype "passive"))
      (node (ref "C25") (pin "1") (pinfunction "1_1") (pintype "passive"))
      (node (ref "C26") (pin "1") (pinfunction "1_1") (pintype "passive"))
      (node (ref "C27") (pin "1") (pinfunction "1_1") (pintype "passive"))
      (node (ref "C28") (pin "1") (pinfunction "1_1") (pintype "passive"))
      (node (ref "C29") (pin "1") (pinfunction "1_1") (pintype "passive"))
      (node (ref "C33") (pin "1") (pinfunction "1_1") (pintype "passive"))
      (node (ref "C34") (pin "2") (pinfunction "2_2") (pintype "passive"))
      (node (ref "L5") (pin "1") (pinfunction "1_1") (pintype "passive"))
      (node (ref "L6") (pin "1") (pinfunction "1_1") (pintype "passive"))
      (node (ref "P5") (pin "3") (pinfunction "3_3") (pintype "passive"))
      (node (ref "P6") (pin "2") (pinfunction "2_2") (pintype "passive"))
      (node (ref "P7") (pin "3") (pinfunction "3_3") (pintype "passive"))
      (node (ref "Q4") (pin "2") (pinfunction "E_2") (pintype "passive"))
      (node (ref "Q5") (pin "2") (pinfunction "E_2") (pintype "passive"))
      (node (ref "Q6") (pin "2") (pinfunction "E_2") (pintype "passive"))
      (node (ref "Q8") (pin "2") (pinfunction "E_2") (pintype "passive"))
      (node (ref "R34") (pin "1") (pinfunction "1_1") (pintype "passive"))
      (node (ref "R43") (pin "1") (pinfunction "1_1") (pintype "passive"))
      (node (ref "R44") (pin "1") (pinfunction "1_1") (pintype "passive"))
      (node (ref "R50") (pin "2") (pinfunction "2_2") (pintype "passive"))
      (node (ref "R53") (pin "2") (pinfunction "2_2") (pintype "passive"))
      (node (ref "R63") (pin "1") (pinfunction "1_1") (pintype "passive"))
      (node (ref "R64") (pin "1") (pinfunction "1_1") (pintype "passive"))
      (node (ref "R65") (pin "1") (pinfunction "1_1") (pintype "passive"))
      (node (ref "R77") (pin "1") (pinfunction "1_1") (pintype "passive"))
      (node (ref "SW1") (pin "2") (pinfunction "2_2") (pintype "passive"))
      (node (ref "U10") (pin "4") (pinfunction "GND1_4") (pintype "passive"))
      (node (ref "U12") (pin "4") (pinfunction "GND_4") (pintype "power_in"))
      (node (ref "U7") (pin "12") (pinfunction "VSSA_12") (pintype "passive"))
      (node (ref "U7") (pin "18") (pinfunction "VSS_18") (pintype "passive"))
      (node (ref "U7") (pin "31") (pinfunction "VSS_31") (pintype "passive"))
      (node (ref "U7") (pin "47") (pinfunction "VSS_47") (pintype "passive"))
      (node (ref "U7") (pin "63") (pinfunction "VSS_63") (pintype "passive"))
      (node (ref "U8") (pin "5") (pinfunction "GND_5") (pintype "power_in"))
    )
    (net (code "46") (name "GND_ISO") (class "Default")
      (node (ref "U10") (pin "5") (pinfunction "GND2_5") (pintype "passive"))
      (node (ref "U10") (pin "7") (pinfunction "GND2_7") (pintype "passive"))
      (node (ref "U11") (pin "3") (pinfunction "I_RET_3") (pintype "power_in"))
    )
    (net (code "47") (name "Net-(D7-K)") (class "Default")
      (node (ref "D7") (pin "2") (pinfunction "K_2") (pintype "passive"))
      (node (ref "R56") (pin "1") (pinfunction "1_1") (pintype "passive"))
    )
    (net (code "48") (name "Net-(D8-K)") (class "Default")
      (node (ref "D8") (pin "2") (pinfunction "K_2") (pintype "passive"))
      (node (ref "R61") (pin "1") (pinfunction "1_1") (pintype "passive"))
    )
    (net (code "49") (name "Net-(D11-G)") (class "Default")
      (node (ref "D11") (pin "1") (pinfunction "G_1") (pintype "passive"))
      (node (ref "Q8") (pin "3") (pinfunction "C_3") (pintype "passive"))
      (node (ref "R74") (pin "2") (pinfunction "2_2") (pintype "passive"))
    )
    (net (code "50") (name "Net-(D12-A)") (class "Default")
      (node (ref "C34") (pin "1") (pinfunction "1_1") (pintype "passive"))
      (node (ref "D12") (pin "1") (pinfunction "A_1") (pintype "passive"))
      (node (ref "D13") (pin "2") (pinfunction "K_2") (pintype "passive"))
    )
    (net (code "51") (name "Net-(D13-A)") (class "Default")
      (node (ref "D13") (pin "1") (pinfunction "A_1") (pintype "passive"))
      (node (ref "R75") (pin "1") (pinfunction "1_1") (pintype "passive"))
    )
    (net (code "52") (name "Net-(L5-Pad2)") (class "Default")
      (node (ref "L5") (pin "2") (pinfunction "2_2") (pintype "passive"))
      (node (ref "P8") (pin "3") (pinfunction "3_3") (pintype "passive"))
    )
    (net (code "53") (name "Net-(P6-Pad3)") (class "Default")
      (node (ref "P6") (pin "3") (pinfunction "3_3") (pintype "power_in"))
      (node (ref "R41") (pin "2") (pinfunction "2_2") (pintype "passive"))
    )
    (net (code "54") (name "Net-(P6-Pad4)") (class "Default")
      (node (ref "P6") (pin "4") (pinfunction "4_4") (pintype "power_in"))
      (node (ref "R42") (pin "2") (pinfunction "2_2") (pintype "passive"))
    )
    (net (code "55") (name "Net-(P6-Pad5)") (class "Default")
      (node (ref "P6") (pin "5") (pinfunction "5_5") (pintype "power_in"))
      (node (ref "R45") (pin "2") (pinfunction "2_2") (pintype "passive"))
    )
    (net (code "56") (name "Net-(Q4-B)") (class "Default")
      (node (ref "Q4") (pin "1") (pinfunction "B_1") (pintype "passive"))
      (node (ref "R39") (pin "2") (pinfunction "2_2") (pintype "passive"))
      (node (ref "R43") (pin "2") (pinfunction "2_2") (pintype "passive"))
    )
    (net (code "57") (name "Net-(Q4-C)") (class "Default")
      (node (ref "Q4") (pin "3") (pinfunction "C_3") (pintype "passive"))
      (node (ref "R35") (pin "1") (pinfunction "1_1") (pintype "passive"))
      (node (ref "R37") (pin "1") (pinfunction "1_1") (pintype "passive"))
    )
    (net (code "58") (name "Net-(Q5-B)") (class "Default")
      (node (ref "Q5") (pin "1") (pinfunction "B_1") (pintype "passive"))
      (node (ref "R40") (pin "2") (pinfunction "2_2") (pintype "passive"))
      (node (ref "R44") (pin "2") (pinfunction "2_2") (pintype "passive"))
    )
    (net (code "59") (name "Net-(Q5-C)") (class "Default")
      (node (ref "Q5") (pin "3") (pinfunction "C_3") (pintype "passive"))
      (node (ref "R36") (pin "1") (pinfunction "1_1") (pintype "passive"))
      (node (ref "R38") (pin "1") (pinfunction "1_1") (pintype "passive"))
    )
    (net (code "60") (name "Net-(Q6-B)") (class "Default")
      (node (ref "Q6") (pin "1") (pinfunction "B_1") (pintype "passive"))
      (node (ref "R60") (pin "2") (pinfunction "2_2") (pintype "passive"))
      (node (ref "R63") (pin "2") (pinfunction "2_2") (pintype "passive"))
    )
    (net (code "61") (name "Net-(Q7-B)") (class "Default")
      (node (ref "Q7") (pin "1") (pinfunction "B_1") (pintype "passive"))
      (node (ref "U11") (pin "6") (pinfunction "BASE_6") (pintype "passive"))
    )
    (net (code "62") (name "Net-(Q7-E)") (class "Default")
      (node (ref "Q7") (pin "2") (pinfunction "E_2") (pintype "passive"))
      (node (ref "U11") (pin "5") (pinfunction "EMITTER_5") (pintype "passive"))
    )
    (net (code "63") (name "Net-(Q8-B)") (class "Default")
      (node (ref "Q8") (pin "1") (pinfunction "B_1") (pintype "passive"))
      (node (ref "R76") (pin "2") (pinfunction "2_2") (pintype "passive"))
      (node (ref "R77") (pin "2") (pinfunction "2_2") (pintype "passive"))
    )
    (net (code "64") (name "Net-(R71-Pad2)") (class "Default")
      (node (ref "R71") (pin "2") (pinfunction "2_2") (pintype "passive"))
      (node (ref "R72") (pin "1") (pinfunction "1_1") (pintype "passive"))
    )
    (net (code "65") (name "Net-(U7A-BOOT0)") (class "Default")
      (node (ref "R50") (pin "1") (pinfunction "1_1") (pintype "passive"))
      (node (ref "U7") (pin "60") (pinfunction "BOOT0_60") (pintype "passive"))
    )
    (net (code "66") (name "Net-(U7A-NRST)") (class "Default")
      (node (ref "R52") (pin "2") (pinfunction "2_2") (pintype "passive"))
      (node (ref "U7") (pin "7") (pinfunction "NRST_7") (pintype "passive"))
    )
    (net (code "67") (name "Net-(U7A-PC1{slash}ADC11)") (class "Default")
      (node (ref "R33") (pin "1") (pinfunction "1_1") (pintype "passive"))
      (node (ref "R34") (pin "2") (pinfunction "2_2") (pintype "passive"))
      (node (ref "U7") (pin "9") (pinfunction "PC1/ADC11_9") (pintype "passive"))
    )
    (net (code "68") (name "Net-(U8-A)") (class "Default")
      (node (ref "F3") (pin "1") (pinfunction "1_1") (pintype "passive"))
      (node (ref "R57") (pin "1") (pinfunction "1_1") (pintype "passive"))
      (node (ref "R62") (pin "2") (pinfunction "2_2") (pintype "passive"))
      (node (ref "U8") (pin "6") (pinfunction "A_6") (pintype "power_in"))
    )
    (net (code "69") (name "Net-(U8-B)") (class "Default")
      (node (ref "F2") (pin "1") (pinfunction "1_1") (pintype "passive"))
      (node (ref "R53") (pin "1") (pinfunction "1_1") (pintype "passive"))
      (node (ref "R57") (pin "2") (pinfunction "2_2") (pintype "passive"))
      (node (ref "U8") (pin "7") (pinfunction "B_7") (pintype "power_in"))
    )
    (net (code "70") (name "Net-(U9-VOUT)") (class "Default")
      (node (ref "R67") (pin "2") (pinfunction "2_2") (pintype "passive"))
      (node (ref "U9") (pin "1") (pinfunction "VOUT_1") (pintype "output"))
    )
    (net (code "71") (name "Net-(U10-OUT)") (class "Default")
      (node (ref "R69") (pin "1") (pinfunction "1_1") (pintype "passive"))
      (node (ref "U10") (pin "6") (pinfunction "OUT_6") (pintype "passive"))
    )
    (net (code "72") (name "Net-(U11-IN)") (class "Default")
      (node (ref "R69") (pin "2") (pinfunction "2_2") (pintype "passive"))
      (node (ref "U11") (pin "2") (pinfunction "IN_2") (pintype "input"))
    )
    (net (code "73") (name "Net-(U11-IOUT)") (class "Default")
      (node (ref "C31") (pin "1") (pinfunction "1_1") (pintype "passive"))
      (node (ref "R71") (pin "1") (pinfunction "1_1") (pintype "passive"))
      (node (ref "U11") (pin "4") (pinfunction "IOUT_4") (pintype "output"))
    )
    (net (code "74") (name "VBAT") (class "Default")
      (node (ref "R59") (pin "2") (pinfunction "2_2") (pintype "passive"))
    )
    (net (code "75") (name "VCC_485") (class "Default")
      (node (ref "C29") (pin "2") (pinfunction "2_2") (pintype "passive"))
      (node (ref "D6") (pin "3") (pinfunction "D_3") (pintype "passive"))
      (node (ref "R55") (pin "2") (pinfunction "2_2") (pintype "passive"))
      (node (ref "R62") (pin "1") (pinfunction "1_1") (pintype "passive"))
      (node (ref "U8") (pin "8") (pinfunction "VCC_8") (pintype "power_in"))
    )
    (net (code "76") (name "VCC_AIN1") (class "Default")
      (node (ref "C30") (pin "1") (pinfunction "1_1") (pintype "passive"))
      (node (ref "D10") (pin "3") (pinfunction "D_3") (pintype "passive"))
      (node (ref "U9") (pin "6") (pinfunction "VCC_6") (pintype "power_in"))
    )
    (net (code "77") (name "VDD_MCU") (class "Default")
      (node (ref "C26") (pin "2") (pinfunction "2_2") (pintype "passive"))
      (node (ref "C27") (pin "2") (pinfunction "2_2") (pintype "passive"))
      (node (ref "C28") (pin "2") (pinfunction "2_2") (pintype "passive"))
      (node (ref "D11") (pin "2") (pinfunction "S_2") (pintype "passive"))
      (node (ref "D12") (pin "2") (pinfunction "K_2") (pintype "passive"))
      (node (ref "R74") (pin "1") (pinfunction "1_1") (pintype "passive"))
      (node (ref "U7") (pin "1") (pinfunction "VDD_1") (pintype "passive"))
      (node (ref "U7") (pin "13") (pinfunction "VDDA_13") (pintype "passive"))
      (node (ref "U7") (pin "19") (pinfunction "VDD_19") (pintype "passive"))
      (node (ref "U7") (pin "32") (pinfunction "VDD_32") (pintype "passive"))
      (node (ref "U7") (pin "48") (pinfunction "VDD_USB_48") (pintype "passive"))
      (node (ref "U7") (pin "64") (pinfunction "VDD_64") (pintype "passive"))
    )
    (net (code "78") (name "VEXT") (class "Default")
      (node (ref "P6") (pin "1") (pinfunction "1_1") (pintype "passive"))
    )
    (net (code "79") (name "VIN 4-20mA") (class "Default")
      (node (ref "C31") (pin "2") (pinfunction "2_2") (pintype "passive"))
      (node (ref "P9") (pin "2") (pinfunction "2_2") (pintype "passive"))
      (node (ref "Q7") (pin "3") (pinfunction "C_3") (pintype "passive"))
      (node (ref "U11") (pin "7") (pinfunction "V+_7") (pintype "power_in"))
    )
    (net (code "80") (name "VIN 24V") (class "Default")
      (node (ref "P10") (pin "1") (pinfunction "1_1") (pintype "passive"))
      (node (ref "R58") (pin "2") (pinfunction "2_2") (pintype "passive"))
    )
    (net (code "81") (name "VREG") (class "Default")
      (node (ref "U10") (pin "8") (pinfunction "VCC2_8") (pintype "passive"))
      (node (ref "U11") (pin "8") (pinfunction "VREG_8") (pintype "power_in"))
    )
    (net (code "82") (name "V_NTC") (class "Default")
      (node (ref "R33") (pin "2") (pinfunction "2_2") (pintype "passive"))
      (node (ref "U7") (pin "62") (pinfunction "PB9_62") (pintype "passive"))
    )
    (net (code "83") (name "unconnected-(U7A-PB3-Pad55)") (class "Default")
      (node (ref "U7") (pin "55") (pinfunction "PB3_55") (pintype "passive"))
    )
    (net (code "84") (name "unconnected-(U7A-PB4-Pad56)") (class "Default")
      (node (ref "U7") (pin "56") (pinfunction "PB4_56") (pintype "passive"))
    )
    (net (code "85") (name "unconnected-(U7A-PB8-Pad61)") (class "Default")
      (node (ref "U7") (pin "61") (pinfunction "PB8_61") (pintype "passive"))
    )
    (net (code "86") (name "unconnected-(U7A-PC0{slash}ADC10-Pad8)") (class "Default")
      (node (ref "U7") (pin "8") (pinfunction "PC0/ADC10_8") (pintype "passive"))
    )
    (net (code "87") (name "unconnected-(U7A-PC6-Pad37)") (class "Default")
      (node (ref "U7") (pin "37") (pinfunction "PC6_37") (pintype "passive"))
    )
    (net (code "88") (name "unconnected-(U7A-PC7-Pad38)") (class "Default")
      (node (ref "U7") (pin "38") (pinfunction "PC7_38") (pintype "passive"))
    )
    (net (code "89") (name "unconnected-(U7A-PC8-Pad39)") (class "Default")
      (node (ref "U7") (pin "39") (pinfunction "PC8_39") (pintype "passive"))
    )
    (net (code "90") (name "unconnected-(U7A-PC9-Pad40)") (class "Default")
      (node (ref "U7") (pin "40") (pinfunction "PC9_40") (pintype "passive"))
    )
    (net (code "91") (name "unconnected-(U7A-PC10-Pad51)") (class "Default")
      (node (ref "U7") (pin "51") (pinfunction "PC10_51") (pintype "passive"))
    )
    (net (code "92") (name "unconnected-(U7A-PC11-Pad52)") (class "Default")
      (node (ref "U7") (pin "52") (pinfunction "PC11_52") (pintype "passive"))
    )
    (net (code "93") (name "unconnected-(U7A-PC12-Pad53)") (class "Default")
      (node (ref "U7") (pin "53") (pinfunction "PC12_53") (pintype "passive"))
    )
    (net (code "94") (name "unconnected-(U7A-PD2-Pad54)") (class "Default")
      (node (ref "U7") (pin "54") (pinfunction "PD2_54") (pintype "passive"))
    )
    (net (code "95") (name "unconnected-(U7A-PH0{slash}OSCIN-Pad5)") (class "Default")
      (node (ref "U7") (pin "5") (pinfunction "PH0/OSCIN_5") (pintype "passive"))
    )
    (net (code "96") (name "unconnected-(U7A-PH1{slash}OSCOUT-Pad6)") (class "Default")
      (node (ref "U7") (pin "6") (pinfunction "PH1/OSCOUT_6") (pintype "passive"))
    )
    (net (code "97") (name "unconnected-(U9-NC-Pad5)") (class "Default")
      (node (ref "U9") (pin "5") (pinfunction "NC_5") (pintype "power_in+no_connect"))
    )
    (net (code "98") (name "unconnected-(U11-NC-Pad1)") (class "Default")
      (node (ref "U11") (pin "1") (pinfunction "NC_1") (pintype "power_in+no_connect"))
    )
  )
)
